# Power_edge.net
KiCad netlist of a schematic drawn in EAGLE
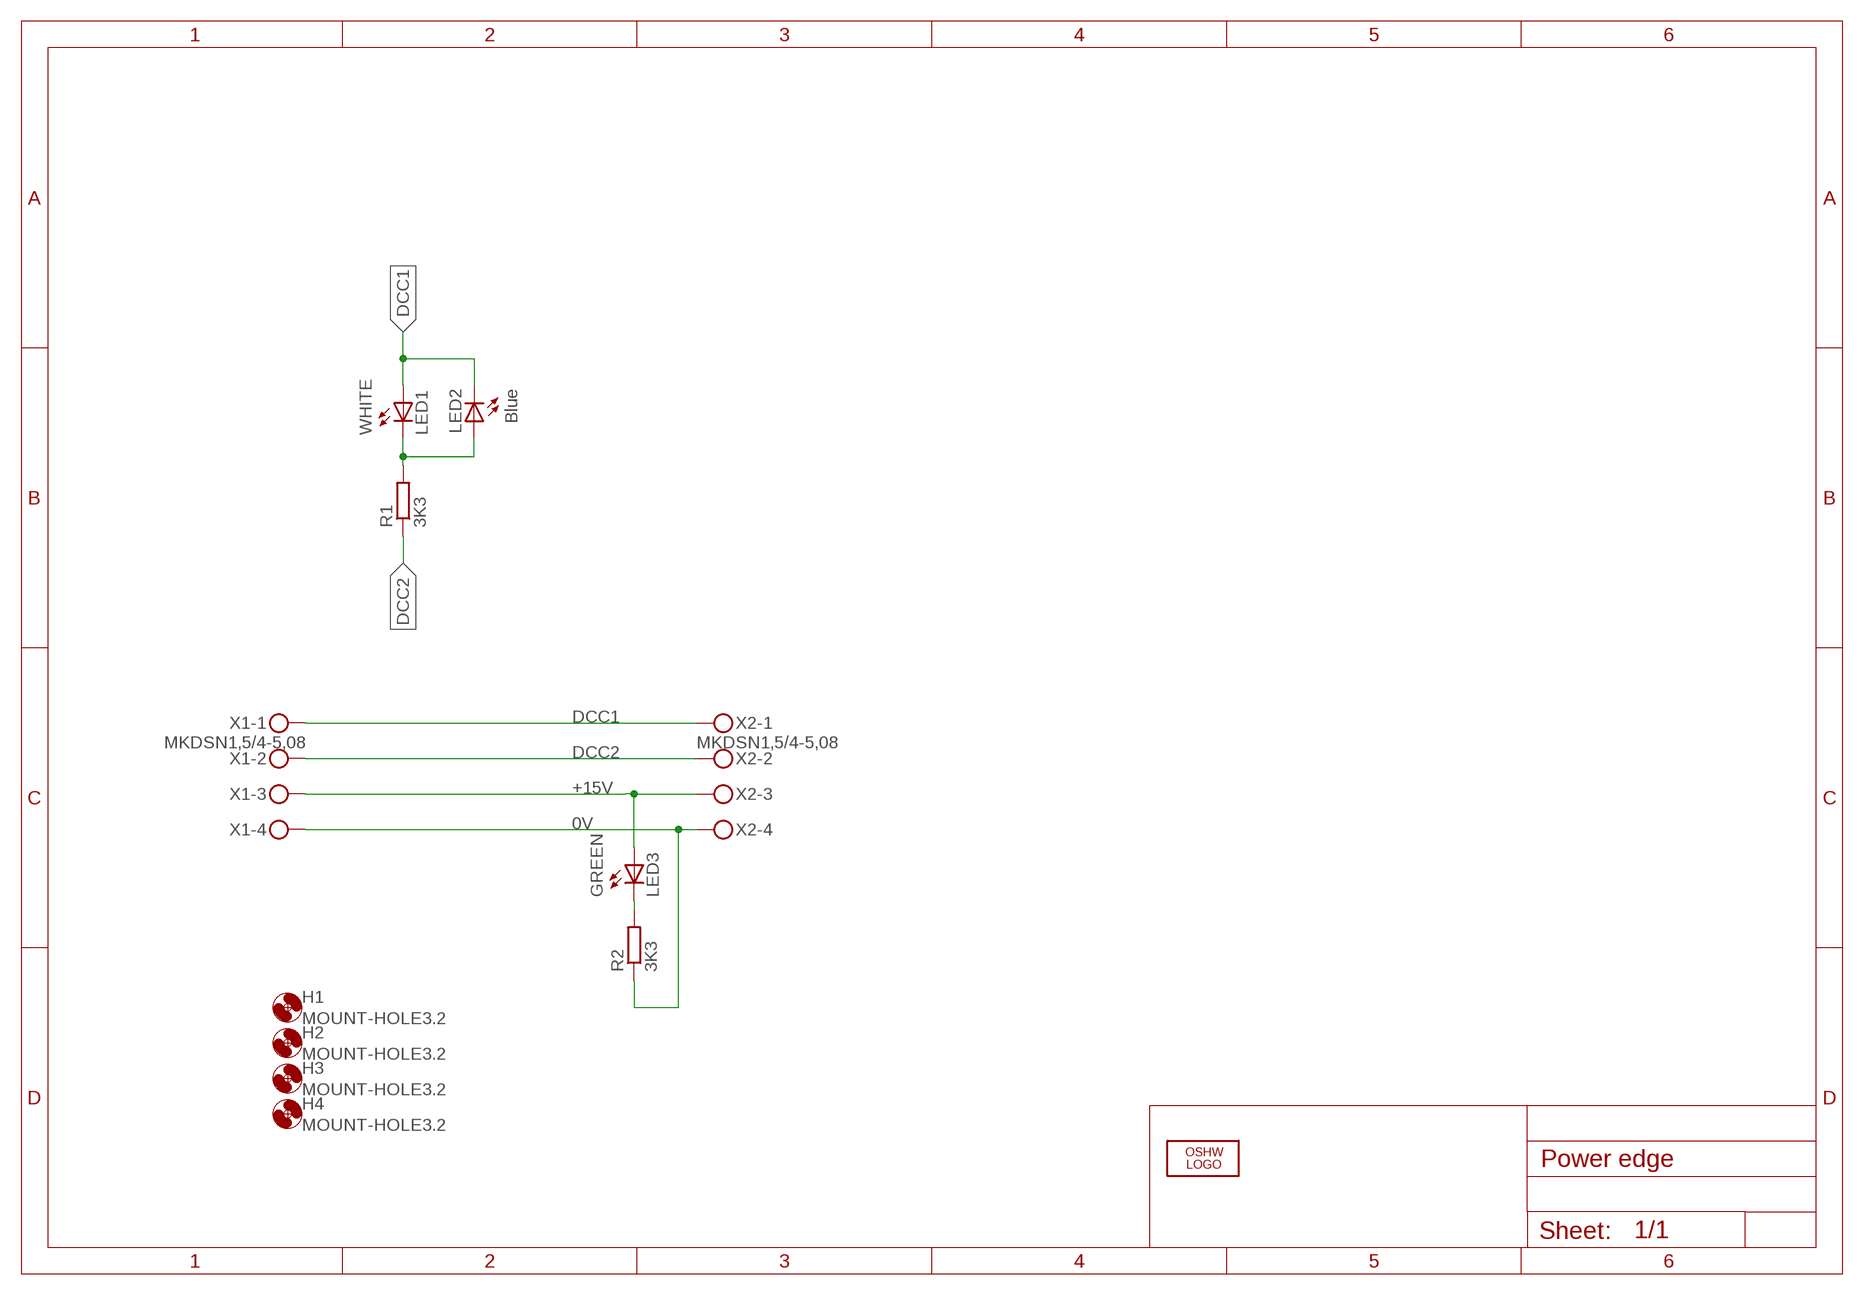
[diagram p0: schematic, sheet 1]

(export (version "E")
  (design (tool "Eeschema 10.0.6"))
  (components
    (comp (ref "H1")
      (value "MOUNT-HOLE3.2")
      (footprint "eagle-import:3,2")
      (libsource (lib "eagle-import") (part "MOUNT-HOLE3.2"))
    )
    (comp (ref "H2")
      (value "MOUNT-HOLE3.2")
      (footprint "eagle-import:3,2")
      (libsource (lib "eagle-import") (part "MOUNT-HOLE3.2"))
    )
    (comp (ref "H3")
      (value "MOUNT-HOLE3.2")
      (footprint "eagle-import:3,2")
      (libsource (lib "eagle-import") (part "MOUNT-HOLE3.2"))
    )
    (comp (ref "H4")
      (value "MOUNT-HOLE3.2")
      (footprint "eagle-import:3,2")
      (libsource (lib "eagle-import") (part "MOUNT-HOLE3.2"))
    )
    (comp (ref "LED1")
      (value "WHITE")
      (footprint "eagle-import:LED3MM")
      (libsource (lib "eagle-import") (part "LED3MM"))
    )
    (comp (ref "LED2")
      (value "Blue")
      (footprint "eagle-import:LED3MM")
      (libsource (lib "eagle-import") (part "LED3MM"))
    )
    (comp (ref "LED3")
      (value "GREEN")
      (footprint "eagle-import:LED3MM")
      (libsource (lib "eagle-import") (part "LED3MM"))
    )
    (comp (ref "LOGO1")
      (value "OSHW_LOGO_6MILX0200-NT")
      (footprint "eagle-import:OSHW_6X200_NOTEXT")
      (libsource (lib "eagle-import") (part "OSHW_LOGO_6MILX0200-NT"))
    )
    (comp (ref "R1")
      (value "3K3")
      (footprint "eagle-import:R0805")
      (libsource (lib "eagle-import") (part "R-EU_R0805"))
    )
    (comp (ref "R2")
      (value "3K3")
      (footprint "eagle-import:R0805")
      (libsource (lib "eagle-import") (part "R-EU_R0805"))
    )
    (comp (ref "X1")
      (value "MKDSN1,5/4-5,08")
      (footprint "eagle-import:MKDSN1,5_4-5,08")
      (fields (field (name "MPN") "SMKDSN1,5/4-5,08"))
      (libsource (lib "eagle-import") (part "MKDSN1,5/4-5,08"))
    )
    (comp (ref "X2")
      (value "MKDSN1,5/4-5,08")
      (footprint "eagle-import:MKDSN1,5_4-5,08")
      (fields (field (name "MPN") "SMKDSN1,5/4-5,08"))
      (libsource (lib "eagle-import") (part "MKDSN1,5/4-5,08"))
    )
  )
  (nets
    (net (code "1") (name "/+15V") (class "Default")
      (node (ref "LED3") (pin "A") (pinfunction "A_A") (pintype "passive"))
      (node (ref "X1") (pin "3") (pinfunction "KL_3") (pintype "passive"))
      (node (ref "X2") (pin "3") (pinfunction "KL_3") (pintype "passive"))
    )
    (net (code "2") (name "/0V") (class "Default")
      (node (ref "R2") (pin "1") (pinfunction "1_1") (pintype "passive"))
      (node (ref "X1") (pin "4") (pinfunction "KL_4") (pintype "passive"))
      (node (ref "X2") (pin "4") (pinfunction "KL_4") (pintype "passive"))
    )
    (net (code "3") (name "DCC1") (class "Default")
      (node (ref "LED1") (pin "A") (pinfunction "A_A") (pintype "passive"))
      (node (ref "LED2") (pin "K") (pinfunction "C_K") (pintype "passive"))
      (node (ref "X1") (pin "1") (pinfunction "KL_1") (pintype "passive"))
      (node (ref "X2") (pin "1") (pinfunction "KL_1") (pintype "passive"))
    )
    (net (code "4") (name "DCC2") (class "Default")
      (node (ref "R1") (pin "1") (pinfunction "1_1") (pintype "passive"))
      (node (ref "X1") (pin "2") (pinfunction "KL_2") (pintype "passive"))
      (node (ref "X2") (pin "2") (pinfunction "KL_2") (pintype "passive"))
    )
    (net (code "5") (name "Net-(LED1-C)") (class "Default")
      (node (ref "LED1") (pin "K") (pinfunction "C_K") (pintype "passive"))
      (node (ref "LED2") (pin "A") (pinfunction "A_A") (pintype "passive"))
      (node (ref "R1") (pin "2") (pinfunction "2_2") (pintype "passive"))
    )
    (net (code "6") (name "Net-(LED3-C)") (class "Default")
      (node (ref "LED3") (pin "K") (pinfunction "C_K") (pintype "passive"))
      (node (ref "R2") (pin "2") (pinfunction "2_2") (pintype "passive"))
    )
  )
)
